# item_2022_analog_01a.net
KiCad netlist of a schematic drawn in EAGLE
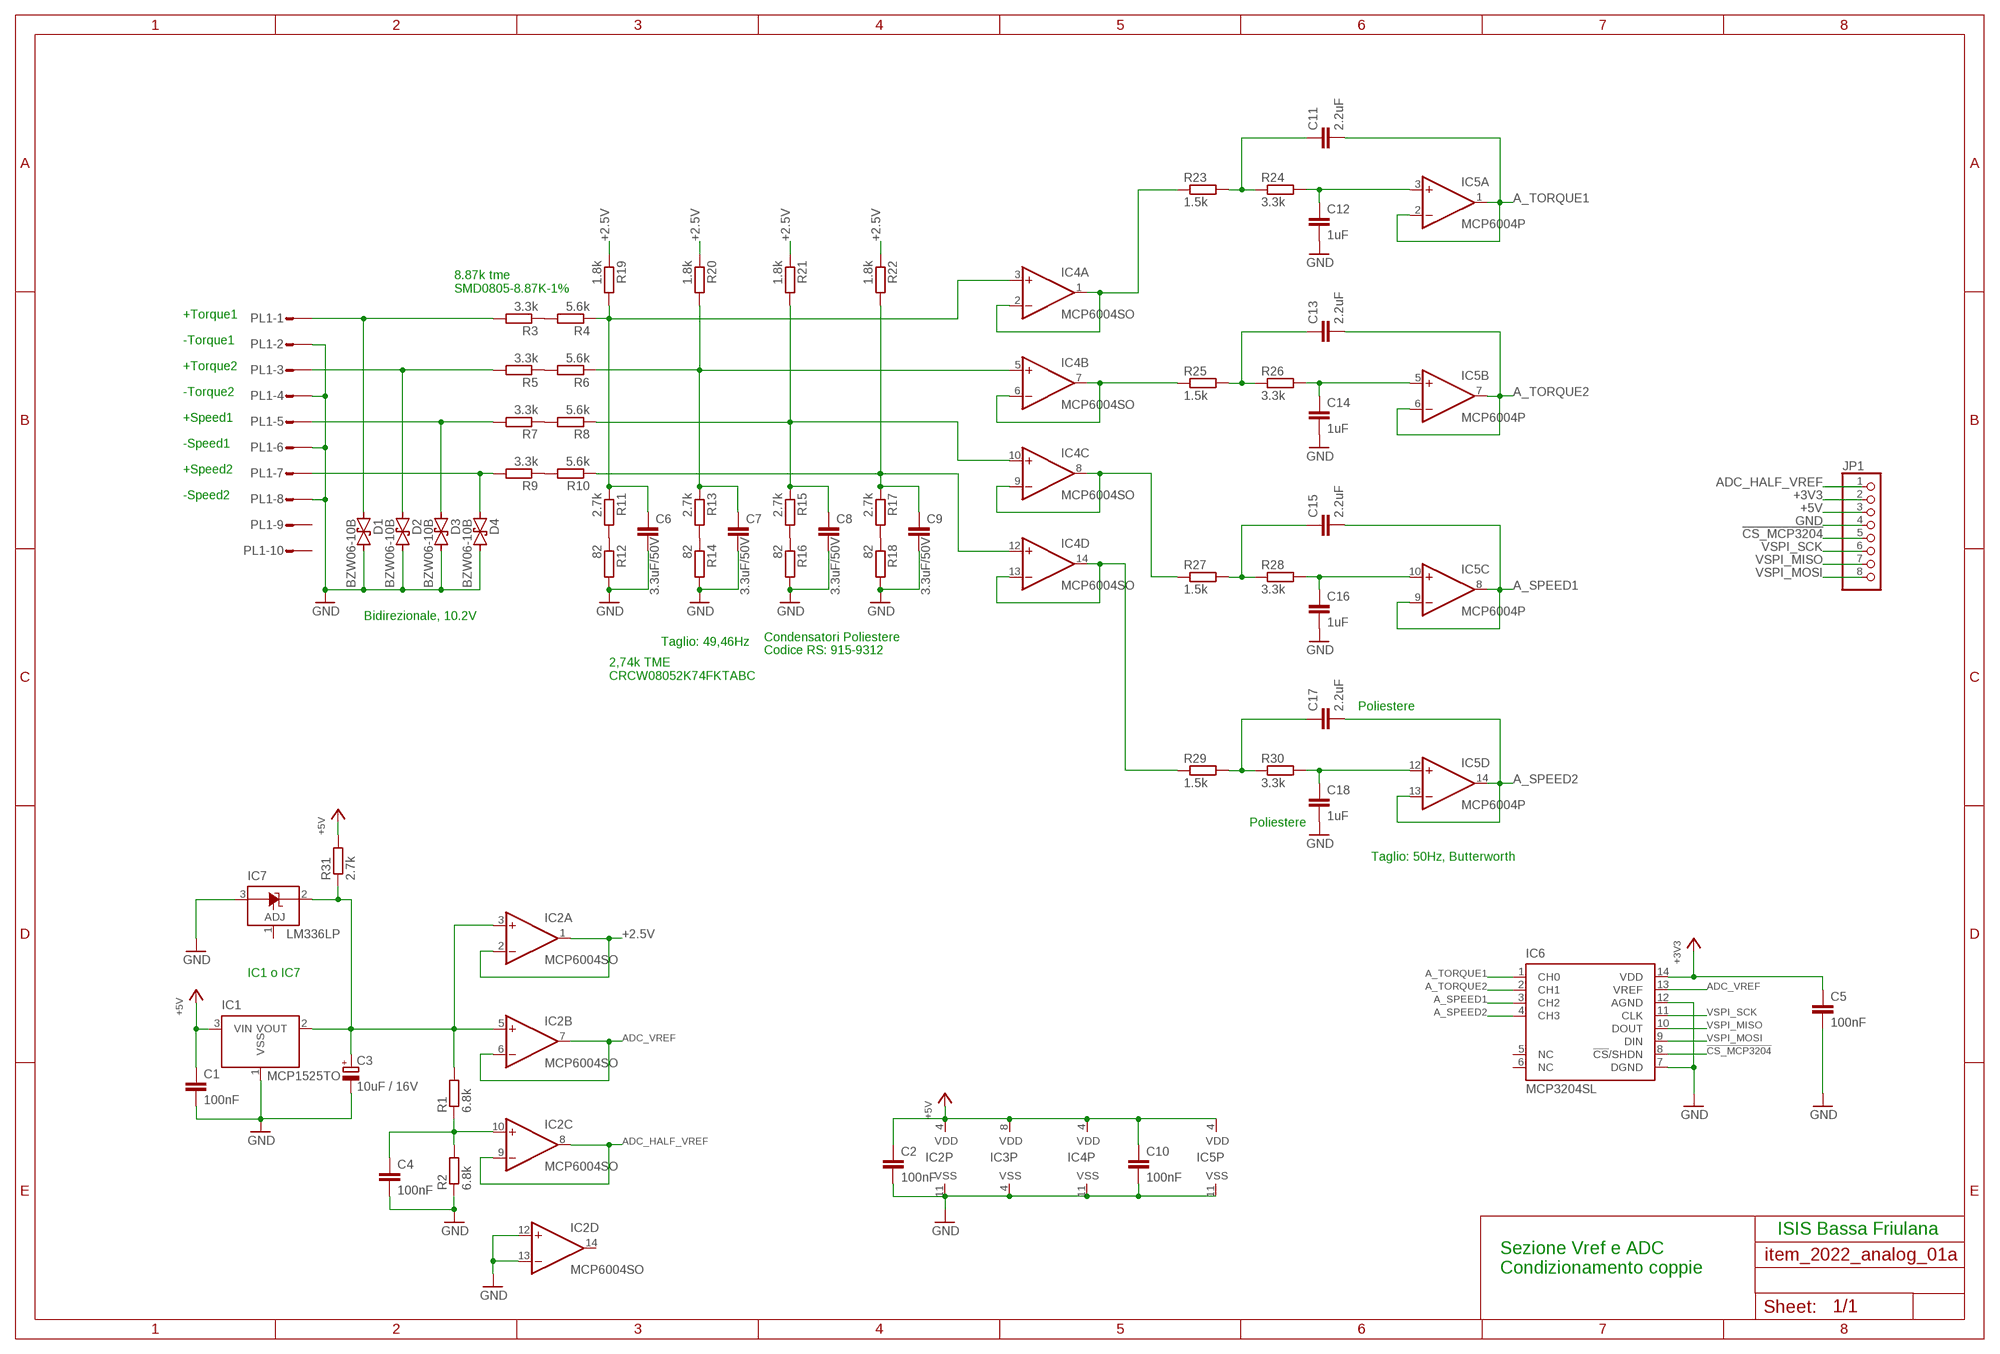
[diagram p0: schematic, sheet 1]

(export (version "E")
  (design (tool "Eeschema 10.0.6"))
  (components
    (comp (ref "C1")
      (value "100nF")
      (footprint "eagle-import:C0805")
      (libsource (lib "eagle-import") (part "C-EUC0805"))
    )
    (comp (ref "C2")
      (value "100nF")
      (footprint "eagle-import:C0805")
      (libsource (lib "eagle-import") (part "C-EUC0805"))
    )
    (comp (ref "C3")
      (value "10uF / 16V")
      (footprint "eagle-import:E2,5-6")
      (libsource (lib "eagle-import") (part "CPOL-EUE2.5-6"))
    )
    (comp (ref "C4")
      (value "100nF")
      (footprint "eagle-import:C0805")
      (libsource (lib "eagle-import") (part "C-EUC0805"))
    )
    (comp (ref "C5")
      (value "100nF")
      (footprint "eagle-import:C0805")
      (libsource (lib "eagle-import") (part "C-EUC0805"))
    )
    (comp (ref "C6")
      (value "3.3uF/50V")
      (footprint "eagle-import:C0805")
      (libsource (lib "eagle-import") (part "C-EUC0805"))
    )
    (comp (ref "C7")
      (value "3.3uF/50V")
      (footprint "eagle-import:C0805")
      (libsource (lib "eagle-import") (part "C-EUC0805"))
    )
    (comp (ref "C8")
      (value "3.3uF/50V")
      (footprint "eagle-import:C0805")
      (libsource (lib "eagle-import") (part "C-EUC0805"))
    )
    (comp (ref "C9")
      (value "3.3uF/50V")
      (footprint "eagle-import:C0805")
      (libsource (lib "eagle-import") (part "C-EUC0805"))
    )
    (comp (ref "C10")
      (value "100nF")
      (footprint "eagle-import:C0805")
      (libsource (lib "eagle-import") (part "C-EUC0805"))
    )
    (comp (ref "C11")
      (value "2.2uF")
      (footprint "eagle-import:C0805")
      (libsource (lib "eagle-import") (part "C-EUC0805"))
    )
    (comp (ref "C12")
      (value "1uF")
      (footprint "eagle-import:C0805")
      (libsource (lib "eagle-import") (part "C-EUC0805"))
    )
    (comp (ref "C13")
      (value "2.2uF")
      (footprint "eagle-import:C0805")
      (libsource (lib "eagle-import") (part "C-EUC0805"))
    )
    (comp (ref "C14")
      (value "1uF")
      (footprint "eagle-import:C0805")
      (libsource (lib "eagle-import") (part "C-EUC0805"))
    )
    (comp (ref "C15")
      (value "2.2uF")
      (footprint "eagle-import:C0805")
      (libsource (lib "eagle-import") (part "C-EUC0805"))
    )
    (comp (ref "C16")
      (value "1uF")
      (footprint "eagle-import:C0805")
      (libsource (lib "eagle-import") (part "C-EUC0805"))
    )
    (comp (ref "C17")
      (value "2.2uF")
      (footprint "eagle-import:C0805")
      (libsource (lib "eagle-import") (part "C-EUC0805"))
    )
    (comp (ref "C18")
      (value "1uF")
      (footprint "eagle-import:C0805")
      (libsource (lib "eagle-import") (part "C-EUC0805"))
    )
    (comp (ref "D1")
      (value "BZW06-10B")
      (footprint "eagle-import:F126Z12")
      (libsource (lib "eagle-import") (part "BZW04XXB"))
    )
    (comp (ref "D2")
      (value "BZW06-10B")
      (footprint "eagle-import:F126Z12")
      (libsource (lib "eagle-import") (part "BZW04XXB"))
    )
    (comp (ref "D3")
      (value "BZW06-10B")
      (footprint "eagle-import:F126Z12")
      (libsource (lib "eagle-import") (part "BZW04XXB"))
    )
    (comp (ref "D4")
      (value "BZW06-10B")
      (footprint "eagle-import:F126Z12")
      (libsource (lib "eagle-import") (part "BZW04XXB"))
    )
    (comp (ref "IC1")
      (value "MCP1525TO")
      (footprint "eagle-import:TO92")
      (libsource (lib "eagle-import") (part "MCP1525TO"))
    )
    (comp (ref "IC2")
      (value "MCP6004SO")
      (footprint "eagle-import:SO14")
      (libsource (lib "eagle-import") (part "MCP6004SO"))
    )
    (comp (ref "IC3")
      (value "MCP6002SO")
      (footprint "eagle-import:SO08")
      (libsource (lib "eagle-import") (part "MCP6002SO"))
    )
    (comp (ref "IC4")
      (value "MCP6004SO")
      (footprint "eagle-import:SO14")
      (libsource (lib "eagle-import") (part "MCP6004SO"))
    )
    (comp (ref "IC5")
      (value "MCP6004P")
      (footprint "eagle-import:DIL14")
      (libsource (lib "eagle-import") (part "MCP6004P"))
    )
    (comp (ref "IC6")
      (value "MCP3204SL")
      (footprint "eagle-import:SO14")
      (libsource (lib "eagle-import") (part "MCP3204SL"))
    )
    (comp (ref "IC7")
      (value "LM336LP")
      (footprint "eagle-import:TO92")
      (libsource (lib "eagle-import") (part "LM336LP"))
    )
    (comp (ref "JP1")
      (value "PINHD-1X8")
      (footprint "eagle-import:1X08")
      (libsource (lib "eagle-import") (part "PINHD-1X8"))
    )
    (comp (ref "PL1")
      (value "10VS")
      (footprint "eagle-import:10V")
      (libsource (lib "eagle-import") (part "10VS"))
    )
    (comp (ref "R1")
      (value "6.8k")
      (footprint "eagle-import:R0805")
      (libsource (lib "eagle-import") (part "rcl_LargePads_R-EU_R0805"))
    )
    (comp (ref "R2")
      (value "6.8k")
      (footprint "eagle-import:R0805")
      (libsource (lib "eagle-import") (part "rcl_LargePads_R-EU_R0805"))
    )
    (comp (ref "R3")
      (value "3.3k")
      (footprint "eagle-import:R0805")
      (libsource (lib "eagle-import") (part "rcl_LargePads_R-EU_R0805"))
    )
    (comp (ref "R4")
      (value "5.6k")
      (footprint "eagle-import:0207_10")
      (libsource (lib "eagle-import") (part "rcl_LargePads_R-EU_0207/10"))
    )
    (comp (ref "R5")
      (value "3.3k")
      (footprint "eagle-import:0207_10")
      (libsource (lib "eagle-import") (part "rcl_LargePads_R-EU_0207/10"))
    )
    (comp (ref "R6")
      (value "5.6k")
      (footprint "eagle-import:0207_10")
      (libsource (lib "eagle-import") (part "rcl_LargePads_R-EU_0207/10"))
    )
    (comp (ref "R7")
      (value "3.3k")
      (footprint "eagle-import:0207_10")
      (libsource (lib "eagle-import") (part "rcl_LargePads_R-EU_0207/10"))
    )
    (comp (ref "R8")
      (value "5.6k")
      (footprint "eagle-import:0207_10")
      (libsource (lib "eagle-import") (part "rcl_LargePads_R-EU_0207/10"))
    )
    (comp (ref "R9")
      (value "3.3k")
      (footprint "eagle-import:0207_10")
      (libsource (lib "eagle-import") (part "rcl_LargePads_R-EU_0207/10"))
    )
    (comp (ref "R10")
      (value "5.6k")
      (footprint "eagle-import:0207_10")
      (libsource (lib "eagle-import") (part "rcl_LargePads_R-EU_0207/10"))
    )
    (comp (ref "R11")
      (value "2.7k")
      (footprint "eagle-import:R0805")
      (libsource (lib "eagle-import") (part "rcl_LargePads_R-EU_R0805"))
    )
    (comp (ref "R12")
      (value "82")
      (footprint "eagle-import:R0805")
      (libsource (lib "eagle-import") (part "rcl_LargePads_R-EU_R0805"))
    )
    (comp (ref "R13")
      (value "2.7k")
      (footprint "eagle-import:R0805")
      (libsource (lib "eagle-import") (part "rcl_LargePads_R-EU_R0805"))
    )
    (comp (ref "R14")
      (value "82")
      (footprint "eagle-import:R0805")
      (libsource (lib "eagle-import") (part "rcl_LargePads_R-EU_R0805"))
    )
    (comp (ref "R15")
      (value "2.7k")
      (footprint "eagle-import:R0805")
      (libsource (lib "eagle-import") (part "rcl_LargePads_R-EU_R0805"))
    )
    (comp (ref "R16")
      (value "82")
      (footprint "eagle-import:R0805")
      (libsource (lib "eagle-import") (part "rcl_LargePads_R-EU_R0805"))
    )
    (comp (ref "R17")
      (value "2.7k")
      (footprint "eagle-import:R0805")
      (libsource (lib "eagle-import") (part "rcl_LargePads_R-EU_R0805"))
    )
    (comp (ref "R18")
      (value "82")
      (footprint "eagle-import:R0805")
      (libsource (lib "eagle-import") (part "rcl_LargePads_R-EU_R0805"))
    )
    (comp (ref "R19")
      (value "1.8k")
      (footprint "eagle-import:R0805")
      (libsource (lib "eagle-import") (part "rcl_LargePads_R-EU_R0805"))
    )
    (comp (ref "R20")
      (value "1.8k")
      (footprint "eagle-import:R0805")
      (libsource (lib "eagle-import") (part "rcl_LargePads_R-EU_R0805"))
    )
    (comp (ref "R21")
      (value "1.8k")
      (footprint "eagle-import:R0805")
      (libsource (lib "eagle-import") (part "rcl_LargePads_R-EU_R0805"))
    )
    (comp (ref "R22")
      (value "1.8k")
      (footprint "eagle-import:R0805")
      (libsource (lib "eagle-import") (part "rcl_LargePads_R-EU_R0805"))
    )
    (comp (ref "R23")
      (value "1.5k")
      (footprint "eagle-import:R0805")
      (libsource (lib "eagle-import") (part "rcl_LargePads_R-EU_R0805"))
    )
    (comp (ref "R24")
      (value "3.3k")
      (footprint "eagle-import:R0805")
      (libsource (lib "eagle-import") (part "rcl_LargePads_R-EU_R0805"))
    )
    (comp (ref "R25")
      (value "1.5k")
      (footprint "eagle-import:R0805")
      (libsource (lib "eagle-import") (part "rcl_LargePads_R-EU_R0805"))
    )
    (comp (ref "R26")
      (value "3.3k")
      (footprint "eagle-import:R0805")
      (libsource (lib "eagle-import") (part "rcl_LargePads_R-EU_R0805"))
    )
    (comp (ref "R27")
      (value "1.5k")
      (footprint "eagle-import:R0805")
      (libsource (lib "eagle-import") (part "rcl_LargePads_R-EU_R0805"))
    )
    (comp (ref "R28")
      (value "3.3k")
      (footprint "eagle-import:R0805")
      (libsource (lib "eagle-import") (part "rcl_LargePads_R-EU_R0805"))
    )
    (comp (ref "R29")
      (value "1.5k")
      (footprint "eagle-import:R0805")
      (libsource (lib "eagle-import") (part "rcl_LargePads_R-EU_R0805"))
    )
    (comp (ref "R30")
      (value "3.3k")
      (footprint "eagle-import:R0805")
      (libsource (lib "eagle-import") (part "rcl_LargePads_R-EU_R0805"))
    )
    (comp (ref "R31")
      (value "2.7k")
      (footprint "eagle-import:R0805")
      (libsource (lib "eagle-import") (part "R-EU_R0805"))
    )
  )
  (nets
    (net (code "1") (name "+3V3") (class "Default")
      (node (ref "C5") (pin "1") (pinfunction "1_1") (pintype "passive"))
      (node (ref "IC6") (pin "14") (pinfunction "VDD_14") (pintype "power_in"))
      (node (ref "JP1") (pin "2") (pinfunction "2_2") (pintype "passive"))
    )
    (net (code "2") (name "+5V") (class "Default")
      (node (ref "C1") (pin "1") (pinfunction "1_1") (pintype "passive"))
      (node (ref "C10") (pin "1") (pinfunction "1_1") (pintype "passive"))
      (node (ref "C2") (pin "1") (pinfunction "1_1") (pintype "passive"))
      (node (ref "IC1") (pin "3") (pinfunction "VIN_3") (pintype "input"))
      (node (ref "IC2") (pin "4") (pinfunction "VDD_4") (pintype "power_in"))
      (node (ref "IC3") (pin "8") (pinfunction "VDD_8") (pintype "power_in"))
      (node (ref "IC4") (pin "4") (pinfunction "VDD_4") (pintype "power_in"))
      (node (ref "IC5") (pin "4") (pinfunction "VDD_4") (pintype "power_in"))
      (node (ref "JP1") (pin "3") (pinfunction "3_3") (pintype "passive"))
      (node (ref "R31") (pin "2") (pinfunction "2_2") (pintype "passive"))
    )
    (net (code "3") (name "/+2.5V") (class "Default")
      (node (ref "IC2") (pin "1") (pinfunction "OUT_1") (pintype "output"))
      (node (ref "IC2") (pin "2") (pinfunction "-IN_2") (pintype "input"))
      (node (ref "R19") (pin "1") (pinfunction "1_1") (pintype "passive"))
      (node (ref "R20") (pin "1") (pinfunction "1_1") (pintype "passive"))
      (node (ref "R21") (pin "1") (pinfunction "1_1") (pintype "passive"))
      (node (ref "R22") (pin "1") (pinfunction "1_1") (pintype "passive"))
    )
    (net (code "4") (name "/ADC_HALF_VREF") (class "Default")
      (node (ref "IC2") (pin "8") (pinfunction "OUT_8") (pintype "output"))
      (node (ref "IC2") (pin "9") (pinfunction "-IN_9") (pintype "input"))
      (node (ref "JP1") (pin "1") (pinfunction "1_1") (pintype "passive"))
    )
    (net (code "5") (name "/ADC_VREF") (class "Default")
      (node (ref "IC2") (pin "6") (pinfunction "-IN_6") (pintype "input"))
      (node (ref "IC2") (pin "7") (pinfunction "OUT_7") (pintype "output"))
      (node (ref "IC6") (pin "13") (pinfunction "VREF_13") (pintype "power_in"))
    )
    (net (code "6") (name "/A_SPEED1") (class "Default")
      (node (ref "C15") (pin "2") (pinfunction "2_2") (pintype "passive"))
      (node (ref "IC5") (pin "8") (pinfunction "OUT_8") (pintype "output"))
      (node (ref "IC5") (pin "9") (pinfunction "-IN_9") (pintype "input"))
      (node (ref "IC6") (pin "3") (pinfunction "CH2_3") (pintype "input"))
    )
    (net (code "7") (name "/A_SPEED2") (class "Default")
      (node (ref "C17") (pin "2") (pinfunction "2_2") (pintype "passive"))
      (node (ref "IC5") (pin "13") (pinfunction "-IN_13") (pintype "input"))
      (node (ref "IC5") (pin "14") (pinfunction "OUT_14") (pintype "output"))
      (node (ref "IC6") (pin "4") (pinfunction "CH3_4") (pintype "input"))
    )
    (net (code "8") (name "/A_TORQUE1") (class "Default")
      (node (ref "C11") (pin "2") (pinfunction "2_2") (pintype "passive"))
      (node (ref "IC5") (pin "1") (pinfunction "OUT_1") (pintype "output"))
      (node (ref "IC5") (pin "2") (pinfunction "-IN_2") (pintype "input"))
      (node (ref "IC6") (pin "1") (pinfunction "CH0_1") (pintype "input"))
    )
    (net (code "9") (name "/A_TORQUE2") (class "Default")
      (node (ref "C13") (pin "2") (pinfunction "2_2") (pintype "passive"))
      (node (ref "IC5") (pin "6") (pinfunction "-IN_6") (pintype "input"))
      (node (ref "IC5") (pin "7") (pinfunction "OUT_7") (pintype "output"))
      (node (ref "IC6") (pin "2") (pinfunction "CH1_2") (pintype "input"))
    )
    (net (code "10") (name "/VSPI_MISO") (class "Default")
      (node (ref "IC6") (pin "10") (pinfunction "DOUT_10") (pintype "input"))
      (node (ref "JP1") (pin "7") (pinfunction "7_7") (pintype "passive"))
    )
    (net (code "11") (name "/VSPI_MOSI") (class "Default")
      (node (ref "IC6") (pin "9") (pinfunction "DIN_9") (pintype "input"))
      (node (ref "JP1") (pin "8") (pinfunction "8_8") (pintype "passive"))
    )
    (net (code "12") (name "/VSPI_SCK") (class "Default")
      (node (ref "IC6") (pin "11") (pinfunction "CLK_11") (pintype "input"))
      (node (ref "JP1") (pin "6") (pinfunction "6_6") (pintype "passive"))
    )
    (net (code "13") (name "/~{CS_MCP3204}") (class "Default")
      (node (ref "IC6") (pin "8") (pinfunction "~{CS}/SHDN_8") (pintype "input"))
      (node (ref "JP1") (pin "5") (pinfunction "5_5") (pintype "passive"))
    )
    (net (code "14") (name "GND") (class "Default")
      (node (ref "C1") (pin "2") (pinfunction "2_2") (pintype "passive"))
      (node (ref "C10") (pin "2") (pinfunction "2_2") (pintype "passive"))
      (node (ref "C12") (pin "2") (pinfunction "2_2") (pintype "passive"))
      (node (ref "C14") (pin "2") (pinfunction "2_2") (pintype "passive"))
      (node (ref "C16") (pin "2") (pinfunction "2_2") (pintype "passive"))
      (node (ref "C18") (pin "2") (pinfunction "2_2") (pintype "passive"))
      (node (ref "C2") (pin "2") (pinfunction "2_2") (pintype "passive"))
      (node (ref "C3") (pin "-") (pinfunction "-_-") (pintype "passive"))
      (node (ref "C4") (pin "2") (pinfunction "2_2") (pintype "passive"))
      (node (ref "C5") (pin "2") (pinfunction "2_2") (pintype "passive"))
      (node (ref "C6") (pin "2") (pinfunction "2_2") (pintype "passive"))
      (node (ref "C7") (pin "2") (pinfunction "2_2") (pintype "passive"))
      (node (ref "C8") (pin "2") (pinfunction "2_2") (pintype "passive"))
      (node (ref "C9") (pin "2") (pinfunction "2_2") (pintype "passive"))
      (node (ref "D1") (pin "C") (pinfunction "2_C") (pintype "passive"))
      (node (ref "D2") (pin "C") (pinfunction "2_C") (pintype "passive"))
      (node (ref "D3") (pin "C") (pinfunction "2_C") (pintype "passive"))
      (node (ref "D4") (pin "C") (pinfunction "2_C") (pintype "passive"))
      (node (ref "IC1") (pin "1") (pinfunction "VSS_1") (pintype "power_in"))
      (node (ref "IC2") (pin "11") (pinfunction "VSS_11") (pintype "power_in"))
      (node (ref "IC2") (pin "12") (pinfunction "+IN_12") (pintype "input"))
      (node (ref "IC2") (pin "13") (pinfunction "-IN_13") (pintype "input"))
      (node (ref "IC3") (pin "4") (pinfunction "VSS_4") (pintype "power_in"))
      (node (ref "IC4") (pin "11") (pinfunction "VSS_11") (pintype "power_in"))
      (node (ref "IC5") (pin "11") (pinfunction "VSS_11") (pintype "power_in"))
      (node (ref "IC6") (pin "12") (pinfunction "AGND_12") (pintype "power_in"))
      (node (ref "IC6") (pin "7") (pinfunction "DGND_7") (pintype "power_in"))
      (node (ref "IC7") (pin "3") (pinfunction "A_3") (pintype "input"))
      (node (ref "JP1") (pin "4") (pinfunction "4_4") (pintype "passive"))
      (node (ref "PL1") (pin "2") (pinfunction "S_2") (pintype "passive"))
      (node (ref "PL1") (pin "4") (pinfunction "S_4") (pintype "passive"))
      (node (ref "PL1") (pin "6") (pinfunction "S_6") (pintype "passive"))
      (node (ref "PL1") (pin "8") (pinfunction "S_8") (pintype "passive"))
      (node (ref "R12") (pin "2") (pinfunction "2_2") (pintype "passive"))
      (node (ref "R14") (pin "2") (pinfunction "2_2") (pintype "passive"))
      (node (ref "R16") (pin "2") (pinfunction "2_2") (pintype "passive"))
      (node (ref "R18") (pin "2") (pinfunction "2_2") (pintype "passive"))
      (node (ref "R2") (pin "1") (pinfunction "1_1") (pintype "passive"))
    )
    (net (code "15") (name "Net-(C11-Pad1)") (class "Default")
      (node (ref "C11") (pin "1") (pinfunction "1_1") (pintype "passive"))
      (node (ref "R23") (pin "2") (pinfunction "2_2") (pintype "passive"))
      (node (ref "R24") (pin "1") (pinfunction "1_1") (pintype "passive"))
    )
    (net (code "16") (name "Net-(C13-Pad1)") (class "Default")
      (node (ref "C13") (pin "1") (pinfunction "1_1") (pintype "passive"))
      (node (ref "R25") (pin "2") (pinfunction "2_2") (pintype "passive"))
      (node (ref "R26") (pin "1") (pinfunction "1_1") (pintype "passive"))
    )
    (net (code "17") (name "Net-(C15-Pad1)") (class "Default")
      (node (ref "C15") (pin "1") (pinfunction "1_1") (pintype "passive"))
      (node (ref "R27") (pin "2") (pinfunction "2_2") (pintype "passive"))
      (node (ref "R28") (pin "1") (pinfunction "1_1") (pintype "passive"))
    )
    (net (code "18") (name "Net-(C17-Pad1)") (class "Default")
      (node (ref "C17") (pin "1") (pinfunction "1_1") (pintype "passive"))
      (node (ref "R29") (pin "2") (pinfunction "2_2") (pintype "passive"))
      (node (ref "R30") (pin "1") (pinfunction "1_1") (pintype "passive"))
    )
    (net (code "19") (name "Net-(D1-1)") (class "Default")
      (node (ref "D1") (pin "A") (pinfunction "1_A") (pintype "passive"))
      (node (ref "PL1") (pin "1") (pinfunction "S_1") (pintype "passive"))
      (node (ref "R3") (pin "2") (pinfunction "2_2") (pintype "passive"))
    )
    (net (code "20") (name "Net-(D2-1)") (class "Default")
      (node (ref "D2") (pin "A") (pinfunction "1_A") (pintype "passive"))
      (node (ref "PL1") (pin "3") (pinfunction "S_3") (pintype "passive"))
      (node (ref "R5") (pin "2") (pinfunction "2_2") (pintype "passive"))
    )
    (net (code "21") (name "Net-(D3-1)") (class "Default")
      (node (ref "D3") (pin "A") (pinfunction "1_A") (pintype "passive"))
      (node (ref "PL1") (pin "5") (pinfunction "S_5") (pintype "passive"))
      (node (ref "R7") (pin "2") (pinfunction "2_2") (pintype "passive"))
    )
    (net (code "22") (name "Net-(D4-1)") (class "Default")
      (node (ref "D4") (pin "A") (pinfunction "1_A") (pintype "passive"))
      (node (ref "PL1") (pin "7") (pinfunction "S_7") (pintype "passive"))
      (node (ref "R9") (pin "2") (pinfunction "2_2") (pintype "passive"))
    )
    (net (code "23") (name "Net-(IC1-VOUT)") (class "Default")
      (node (ref "C3") (pin "+") (pinfunction "+_+") (pintype "passive"))
      (node (ref "IC1") (pin "2") (pinfunction "VOUT_2") (pintype "output"))
      (node (ref "IC2") (pin "3") (pinfunction "+IN_3") (pintype "input"))
      (node (ref "IC2") (pin "5") (pinfunction "+IN_5") (pintype "input"))
      (node (ref "IC7") (pin "2") (pinfunction "C_2") (pintype "passive"))
      (node (ref "R1") (pin "2") (pinfunction "2_2") (pintype "passive"))
      (node (ref "R31") (pin "1") (pinfunction "1_1") (pintype "passive"))
    )
    (net (code "24") (name "Net-(IC2C-+IN)") (class "Default")
      (node (ref "C4") (pin "1") (pinfunction "1_1") (pintype "passive"))
      (node (ref "IC2") (pin "10") (pinfunction "+IN_10") (pintype "input"))
      (node (ref "R1") (pin "1") (pinfunction "1_1") (pintype "passive"))
      (node (ref "R2") (pin "2") (pinfunction "2_2") (pintype "passive"))
    )
    (net (code "25") (name "Net-(IC4A-+IN)") (class "Default")
      (node (ref "C6") (pin "1") (pinfunction "1_1") (pintype "passive"))
      (node (ref "IC4") (pin "3") (pinfunction "+IN_3") (pintype "input"))
      (node (ref "R11") (pin "1") (pinfunction "1_1") (pintype "passive"))
      (node (ref "R19") (pin "2") (pinfunction "2_2") (pintype "passive"))
      (node (ref "R4") (pin "1") (pinfunction "1_1") (pintype "passive"))
    )
    (net (code "26") (name "Net-(IC4A--IN)") (class "Default")
      (node (ref "IC4") (pin "1") (pinfunction "OUT_1") (pintype "output"))
      (node (ref "IC4") (pin "2") (pinfunction "-IN_2") (pintype "input"))
      (node (ref "R23") (pin "1") (pinfunction "1_1") (pintype "passive"))
    )
    (net (code "27") (name "Net-(IC4B-+IN)") (class "Default")
      (node (ref "C7") (pin "1") (pinfunction "1_1") (pintype "passive"))
      (node (ref "IC4") (pin "5") (pinfunction "+IN_5") (pintype "input"))
      (node (ref "R13") (pin "1") (pinfunction "1_1") (pintype "passive"))
      (node (ref "R20") (pin "2") (pinfunction "2_2") (pintype "passive"))
      (node (ref "R6") (pin "1") (pinfunction "1_1") (pintype "passive"))
    )
    (net (code "28") (name "Net-(IC4B--IN)") (class "Default")
      (node (ref "IC4") (pin "6") (pinfunction "-IN_6") (pintype "input"))
      (node (ref "IC4") (pin "7") (pinfunction "OUT_7") (pintype "output"))
      (node (ref "R25") (pin "1") (pinfunction "1_1") (pintype "passive"))
    )
    (net (code "29") (name "Net-(IC4C-+IN)") (class "Default")
      (node (ref "C8") (pin "1") (pinfunction "1_1") (pintype "passive"))
      (node (ref "IC4") (pin "10") (pinfunction "+IN_10") (pintype "input"))
      (node (ref "R15") (pin "1") (pinfunction "1_1") (pintype "passive"))
      (node (ref "R21") (pin "2") (pinfunction "2_2") (pintype "passive"))
      (node (ref "R8") (pin "1") (pinfunction "1_1") (pintype "passive"))
    )
    (net (code "30") (name "Net-(IC4C--IN)") (class "Default")
      (node (ref "IC4") (pin "8") (pinfunction "OUT_8") (pintype "output"))
      (node (ref "IC4") (pin "9") (pinfunction "-IN_9") (pintype "input"))
      (node (ref "R27") (pin "1") (pinfunction "1_1") (pintype "passive"))
    )
    (net (code "31") (name "Net-(IC4D-+IN)") (class "Default")
      (node (ref "C9") (pin "1") (pinfunction "1_1") (pintype "passive"))
      (node (ref "IC4") (pin "12") (pinfunction "+IN_12") (pintype "input"))
      (node (ref "R10") (pin "1") (pinfunction "1_1") (pintype "passive"))
      (node (ref "R17") (pin "1") (pinfunction "1_1") (pintype "passive"))
      (node (ref "R22") (pin "2") (pinfunction "2_2") (pintype "passive"))
    )
    (net (code "32") (name "Net-(IC4D--IN)") (class "Default")
      (node (ref "IC4") (pin "13") (pinfunction "-IN_13") (pintype "input"))
      (node (ref "IC4") (pin "14") (pinfunction "OUT_14") (pintype "output"))
      (node (ref "R29") (pin "1") (pinfunction "1_1") (pintype "passive"))
    )
    (net (code "33") (name "Net-(IC5A-+IN)") (class "Default")
      (node (ref "C12") (pin "1") (pinfunction "1_1") (pintype "passive"))
      (node (ref "IC5") (pin "3") (pinfunction "+IN_3") (pintype "input"))
      (node (ref "R24") (pin "2") (pinfunction "2_2") (pintype "passive"))
    )
    (net (code "34") (name "Net-(IC5B-+IN)") (class "Default")
      (node (ref "C14") (pin "1") (pinfunction "1_1") (pintype "passive"))
      (node (ref "IC5") (pin "5") (pinfunction "+IN_5") (pintype "input"))
      (node (ref "R26") (pin "2") (pinfunction "2_2") (pintype "passive"))
    )
    (net (code "35") (name "Net-(IC5C-+IN)") (class "Default")
      (node (ref "C16") (pin "1") (pinfunction "1_1") (pintype "passive"))
      (node (ref "IC5") (pin "10") (pinfunction "+IN_10") (pintype "input"))
      (node (ref "R28") (pin "2") (pinfunction "2_2") (pintype "passive"))
    )
    (net (code "36") (name "Net-(IC5D-+IN)") (class "Default")
      (node (ref "C18") (pin "1") (pinfunction "1_1") (pintype "passive"))
      (node (ref "IC5") (pin "12") (pinfunction "+IN_12") (pintype "input"))
      (node (ref "R30") (pin "2") (pinfunction "2_2") (pintype "passive"))
    )
    (net (code "37") (name "Net-(R3-Pad1)") (class "Default")
      (node (ref "R3") (pin "1") (pinfunction "1_1") (pintype "passive"))
      (node (ref "R4") (pin "2") (pinfunction "2_2") (pintype "passive"))
    )
    (net (code "38") (name "Net-(R5-Pad1)") (class "Default")
      (node (ref "R5") (pin "1") (pinfunction "1_1") (pintype "passive"))
      (node (ref "R6") (pin "2") (pinfunction "2_2") (pintype "passive"))
    )
    (net (code "39") (name "Net-(R7-Pad1)") (class "Default")
      (node (ref "R7") (pin "1") (pinfunction "1_1") (pintype "passive"))
      (node (ref "R8") (pin "2") (pinfunction "2_2") (pintype "passive"))
    )
    (net (code "40") (name "Net-(R10-Pad2)") (class "Default")
      (node (ref "R10") (pin "2") (pinfunction "2_2") (pintype "passive"))
      (node (ref "R9") (pin "1") (pinfunction "1_1") (pintype "passive"))
    )
    (net (code "41") (name "Net-(R11-Pad2)") (class "Default")
      (node (ref "R11") (pin "2") (pinfunction "2_2") (pintype "passive"))
      (node (ref "R12") (pin "1") (pinfunction "1_1") (pintype "passive"))
    )
    (net (code "42") (name "Net-(R13-Pad2)") (class "Default")
      (node (ref "R13") (pin "2") (pinfunction "2_2") (pintype "passive"))
      (node (ref "R14") (pin "1") (pinfunction "1_1") (pintype "passive"))
    )
    (net (code "43") (name "Net-(R15-Pad2)") (class "Default")
      (node (ref "R15") (pin "2") (pinfunction "2_2") (pintype "passive"))
      (node (ref "R16") (pin "1") (pinfunction "1_1") (pintype "passive"))
    )
    (net (code "44") (name "Net-(R17-Pad2)") (class "Default")
      (node (ref "R17") (pin "2") (pinfunction "2_2") (pintype "passive"))
      (node (ref "R18") (pin "1") (pinfunction "1_1") (pintype "passive"))
    )
    (net (code "45") (name "unconnected-(IC2D-OUT-Pad14)") (class "Default")
      (node (ref "IC2") (pin "14") (pinfunction "OUT_14") (pintype "output"))
    )
    (net (code "46") (name "unconnected-(IC6-NC-Pad5)") (class "Default")
      (node (ref "IC6") (pin "5") (pinfunction "NC_5") (pintype "no_connect"))
    )
    (net (code "47") (name "unconnected-(IC6-NC-Pad6)") (class "Default")
      (node (ref "IC6") (pin "6") (pinfunction "NC_6") (pintype "no_connect"))
    )
    (net (code "48") (name "unconnected-(IC7-ADJ-Pad1)") (class "Default")
      (node (ref "IC7") (pin "1") (pinfunction "ADJ_1") (pintype "input"))
    )
    (net (code "49") (name "unconnected-(PL1B-S-Pad10)") (class "Default")
      (node (ref "PL1") (pin "10") (pinfunction "S_10") (pintype "passive"))
    )
    (net (code "50") (name "unconnected-(PL1J-S-Pad9)") (class "Default")
      (node (ref "PL1") (pin "9") (pinfunction "S_9") (pintype "passive"))
    )
  )
)
